# driverMotor.net
KiCad netlist of a schematic drawn in EAGLE
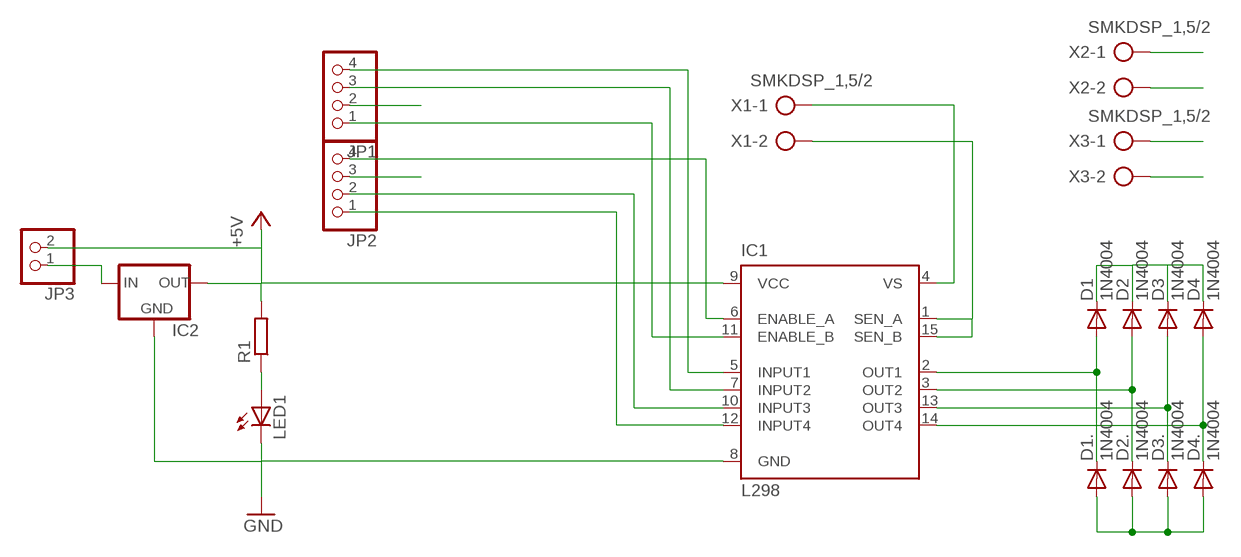
[diagram p0: schematic, sheet 1]

(export (version "E")
  (design (tool "Eeschema 10.0.6"))
  (components
    (comp (ref "D1")
      (value "1N4004")
      (footprint "eagle-import:DO41-10")
      (libsource (lib "eagle-import") (part "1N4004"))
    )
    (comp (ref "D1.")
      (value "1N4004")
      (footprint "eagle-import:DO41-10")
      (libsource (lib "eagle-import") (part "1N4004"))
    )
    (comp (ref "D2")
      (value "1N4004")
      (footprint "eagle-import:DO41-10")
      (libsource (lib "eagle-import") (part "1N4004"))
    )
    (comp (ref "D2.")
      (value "1N4004")
      (footprint "eagle-import:DO41-10")
      (libsource (lib "eagle-import") (part "1N4004"))
    )
    (comp (ref "D3")
      (value "1N4004")
      (footprint "eagle-import:DO41-10")
      (libsource (lib "eagle-import") (part "1N4004"))
    )
    (comp (ref "D3.")
      (value "1N4004")
      (footprint "eagle-import:DO41-10")
      (libsource (lib "eagle-import") (part "1N4004"))
    )
    (comp (ref "D4")
      (value "1N4004")
      (footprint "eagle-import:DO41-10")
      (libsource (lib "eagle-import") (part "1N4004"))
    )
    (comp (ref "D4.")
      (value "1N4004")
      (footprint "eagle-import:DO41-10")
      (libsource (lib "eagle-import") (part "1N4004"))
    )
    (comp (ref "IC1")
      (value "L298")
      (footprint "eagle-import:MULTIWATT-15")
      (libsource (lib "eagle-import") (part "L298"))
    )
    (comp (ref "IC2")
      (value "78MXXS")
      (footprint "eagle-import:78MXXS")
      (libsource (lib "eagle-import") (part "78MXXS"))
    )
    (comp (ref "JP1")
      (value "PINHD-1X4")
      (footprint "eagle-import:1X04")
      (libsource (lib "eagle-import") (part "PINHD-1X4"))
    )
    (comp (ref "JP2")
      (value "PINHD-1X4")
      (footprint "eagle-import:1X04")
      (libsource (lib "eagle-import") (part "PINHD-1X4"))
    )
    (comp (ref "JP3")
      (value "PINHD-1X2")
      (footprint "eagle-import:1X02")
      (libsource (lib "eagle-import") (part "PINHD-1X2"))
    )
    (comp (ref "LED1")
      (value "LED5MM")
      (footprint "eagle-import:LED5MM")
      (libsource (lib "eagle-import") (part "LED5MM"))
    )
    (comp (ref "R1")
      (value "R-EU_0411/12")
      (footprint "eagle-import:0411_12")
      (libsource (lib "eagle-import") (part "R-EU_0411/12"))
    )
    (comp (ref "X1")
      (value "SMKDSP_1,5/2")
      (footprint "eagle-import:SMKDSP_1,5_2")
      (fields (field (name "MF") "FARNELL") (field (name "MPN") "1733570"))
      (libsource (lib "eagle-import") (part "SMKDSP_1,5/2"))
    )
    (comp (ref "X2")
      (value "SMKDSP_1,5/2")
      (footprint "eagle-import:SMKDSP_1,5_2")
      (fields (field (name "MF") "FARNELL") (field (name "MPN") "1733570"))
      (libsource (lib "eagle-import") (part "SMKDSP_1,5/2"))
    )
    (comp (ref "X3")
      (value "SMKDSP_1,5/2")
      (footprint "eagle-import:SMKDSP_1,5_2")
      (fields (field (name "MF") "FARNELL") (field (name "MPN") "1733570"))
      (libsource (lib "eagle-import") (part "SMKDSP_1,5/2"))
    )
  )
  (nets
    (net (code "1") (name "+5V") (class "Default")
      (node (ref "IC1") (pin "9") (pinfunction "VCC_9") (pintype "power_in"))
      (node (ref "IC2") (pin "OUT") (pinfunction "OUT_OUT") (pintype "passive"))
      (node (ref "JP1") (pin "2") (pinfunction "2_2") (pintype "passive"))
      (node (ref "JP3") (pin "2") (pinfunction "2_2") (pintype "passive"))
      (node (ref "R1") (pin "2") (pinfunction "2_2") (pintype "passive"))
    )
    (net (code "2") (name "/MOTOR1_1") (class "Default")
      (node (ref "D1") (pin "A") (pinfunction "A_A") (pintype "passive"))
      (node (ref "D1.") (pin "C") (pinfunction "C_C") (pintype "passive"))
      (node (ref "IC1") (pin "2") (pinfunction "OUT1_2") (pintype "output"))
      (node (ref "X2") (pin "1") (pinfunction "KL_1") (pintype "passive"))
    )
    (net (code "3") (name "/MOTOR1_2") (class "Default")
      (node (ref "D2") (pin "A") (pinfunction "A_A") (pintype "passive"))
      (node (ref "D2.") (pin "C") (pinfunction "C_C") (pintype "passive"))
      (node (ref "IC1") (pin "3") (pinfunction "OUT2_3") (pintype "output"))
      (node (ref "X2") (pin "2") (pinfunction "KL_2") (pintype "passive"))
    )
    (net (code "4") (name "/MOTOR2_1") (class "Default")
      (node (ref "D3") (pin "A") (pinfunction "A_A") (pintype "passive"))
      (node (ref "D3.") (pin "C") (pinfunction "C_C") (pintype "passive"))
      (node (ref "IC1") (pin "13") (pinfunction "OUT3_13") (pintype "output"))
      (node (ref "X3") (pin "1") (pinfunction "KL_1") (pintype "passive"))
    )
    (net (code "5") (name "/MOTOR2_2") (class "Default")
      (node (ref "D4") (pin "A") (pinfunction "A_A") (pintype "passive"))
      (node (ref "D4.") (pin "C") (pinfunction "C_C") (pintype "passive"))
      (node (ref "IC1") (pin "14") (pinfunction "OUT4_14") (pintype "output"))
      (node (ref "X3") (pin "2") (pinfunction "KL_2") (pintype "passive"))
    )
    (net (code "6") (name "/VS") (class "Default")
      (node (ref "D1") (pin "C") (pinfunction "C_C") (pintype "passive"))
      (node (ref "D2") (pin "C") (pinfunction "C_C") (pintype "passive"))
      (node (ref "D3") (pin "C") (pinfunction "C_C") (pintype "passive"))
      (node (ref "D4") (pin "C") (pinfunction "C_C") (pintype "passive"))
      (node (ref "IC1") (pin "4") (pinfunction "VS_4") (pintype "power_in"))
      (node (ref "X1") (pin "1") (pinfunction "KL_1") (pintype "passive"))
    )
    (net (code "7") (name "GND") (class "Default")
      (node (ref "D1.") (pin "A") (pinfunction "A_A") (pintype "passive"))
      (node (ref "D2.") (pin "A") (pinfunction "A_A") (pintype "passive"))
      (node (ref "D3.") (pin "A") (pinfunction "A_A") (pintype "passive"))
      (node (ref "D4.") (pin "A") (pinfunction "A_A") (pintype "passive"))
      (node (ref "IC1") (pin "1") (pinfunction "SEN_A_1") (pintype "input"))
      (node (ref "IC1") (pin "15") (pinfunction "SEN_B_15") (pintype "input"))
      (node (ref "IC1") (pin "8") (pinfunction "GND_8") (pintype "power_in"))
      (node (ref "IC2") (pin "GND") (pinfunction "GND_GND") (pintype "input"))
      (node (ref "JP2") (pin "3") (pinfunction "3_3") (pintype "passive"))
      (node (ref "LED1") (pin "K") (pinfunction "C_K") (pintype "passive"))
      (node (ref "X1") (pin "2") (pinfunction "KL_2") (pintype "passive"))
    )
    (net (code "8") (name "Net-(IC1-ENABLE_A)") (class "Default")
      (node (ref "IC1") (pin "6") (pinfunction "ENABLE_A_6") (pintype "input"))
      (node (ref "JP2") (pin "4") (pinfunction "4_4") (pintype "passive"))
    )
    (net (code "9") (name "Net-(IC1-ENABLE_B)") (class "Default")
      (node (ref "IC1") (pin "11") (pinfunction "ENABLE_B_11") (pintype "input"))
      (node (ref "JP1") (pin "1") (pinfunction "1_1") (pintype "passive"))
    )
    (net (code "10") (name "Net-(IC1-INPUT1)") (class "Default")
      (node (ref "IC1") (pin "5") (pinfunction "INPUT1_5") (pintype "input"))
      (node (ref "JP1") (pin "4") (pinfunction "4_4") (pintype "passive"))
    )
    (net (code "11") (name "Net-(IC1-INPUT2)") (class "Default")
      (node (ref "IC1") (pin "7") (pinfunction "INPUT2_7") (pintype "input"))
      (node (ref "JP1") (pin "3") (pinfunction "3_3") (pintype "passive"))
    )
    (net (code "12") (name "Net-(IC1-INPUT3)") (class "Default")
      (node (ref "IC1") (pin "10") (pinfunction "INPUT3_10") (pintype "input"))
      (node (ref "JP2") (pin "2") (pinfunction "2_2") (pintype "passive"))
    )
    (net (code "13") (name "Net-(IC1-INPUT4)") (class "Default")
      (node (ref "IC1") (pin "12") (pinfunction "INPUT4_12") (pintype "input"))
      (node (ref "JP2") (pin "1") (pinfunction "1_1") (pintype "passive"))
    )
    (net (code "14") (name "Net-(IC2-PadIN)") (class "Default")
      (node (ref "IC2") (pin "IN") (pinfunction "IN_IN") (pintype "input"))
      (node (ref "JP3") (pin "1") (pinfunction "1_1") (pintype "passive"))
    )
    (net (code "15") (name "Net-(LED1-PadA)") (class "Default")
      (node (ref "LED1") (pin "A") (pinfunction "A_A") (pintype "passive"))
      (node (ref "R1") (pin "1") (pinfunction "1_1") (pintype "passive"))
    )
  )
)
